# tcrt5000.net
KiCad netlist of a schematic drawn in Altium Designer
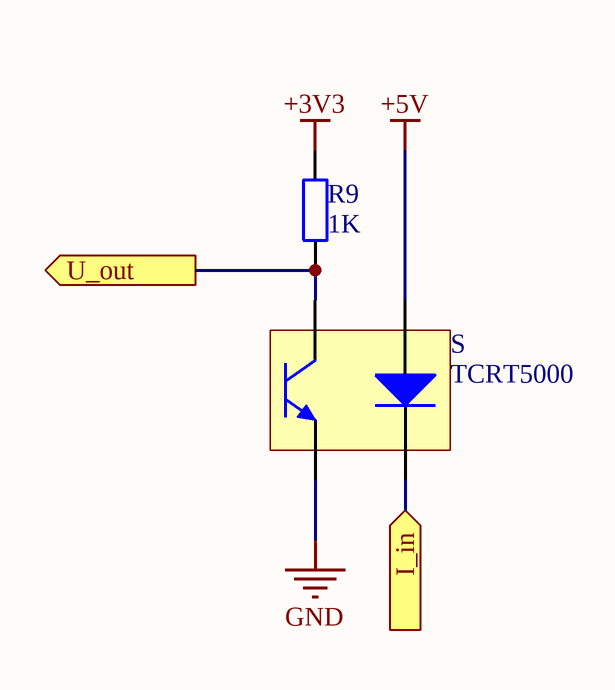
[diagram p0: tcrt5000.SchDoc]

(export (version "E")
  (design (tool "Eeschema 10.0.6"))
  (components
    (comp (ref "R9")
      (value "1K")
      (footprint "FP_0805_RES")
      (description "Resistor")
      (libsource (lib "hallglib") (part "RES"))
    )
    (comp (ref "S")
      (value "TCRT5000")
      (footprint "TCRT5000_REV3")
      (description "Reflective Photo Interrupter")
      (libsource (lib "mb") (part "TCRT5000"))
    )
  )
  (nets
    (net (code "1") (name "+3V3") (class "Default")
      (node (ref "R9") (pin "2") (pinfunction "2_2") (pintype "passive"))
    )
    (net (code "2") (name "+5V") (class "Default")
      (node (ref "S") (pin "A") (pinfunction "A_A") (pintype "passive"))
    )
    (net (code "3") (name "/I_in") (class "Default")
      (node (ref "S") (pin "K") (pinfunction "K_K") (pintype "passive"))
    )
    (net (code "4") (name "/U_out") (class "Default")
      (node (ref "R9") (pin "1") (pinfunction "1_1") (pintype "passive"))
      (node (ref "S") (pin "C") (pinfunction "C_C") (pintype "passive"))
    )
    (net (code "5") (name "GND") (class "Default")
      (node (ref "S") (pin "E") (pinfunction "E_E") (pintype "passive"))
    )
  )
)
